# CaINv2_2.net
KiCad netlist of a schematic drawn in Altium Designer
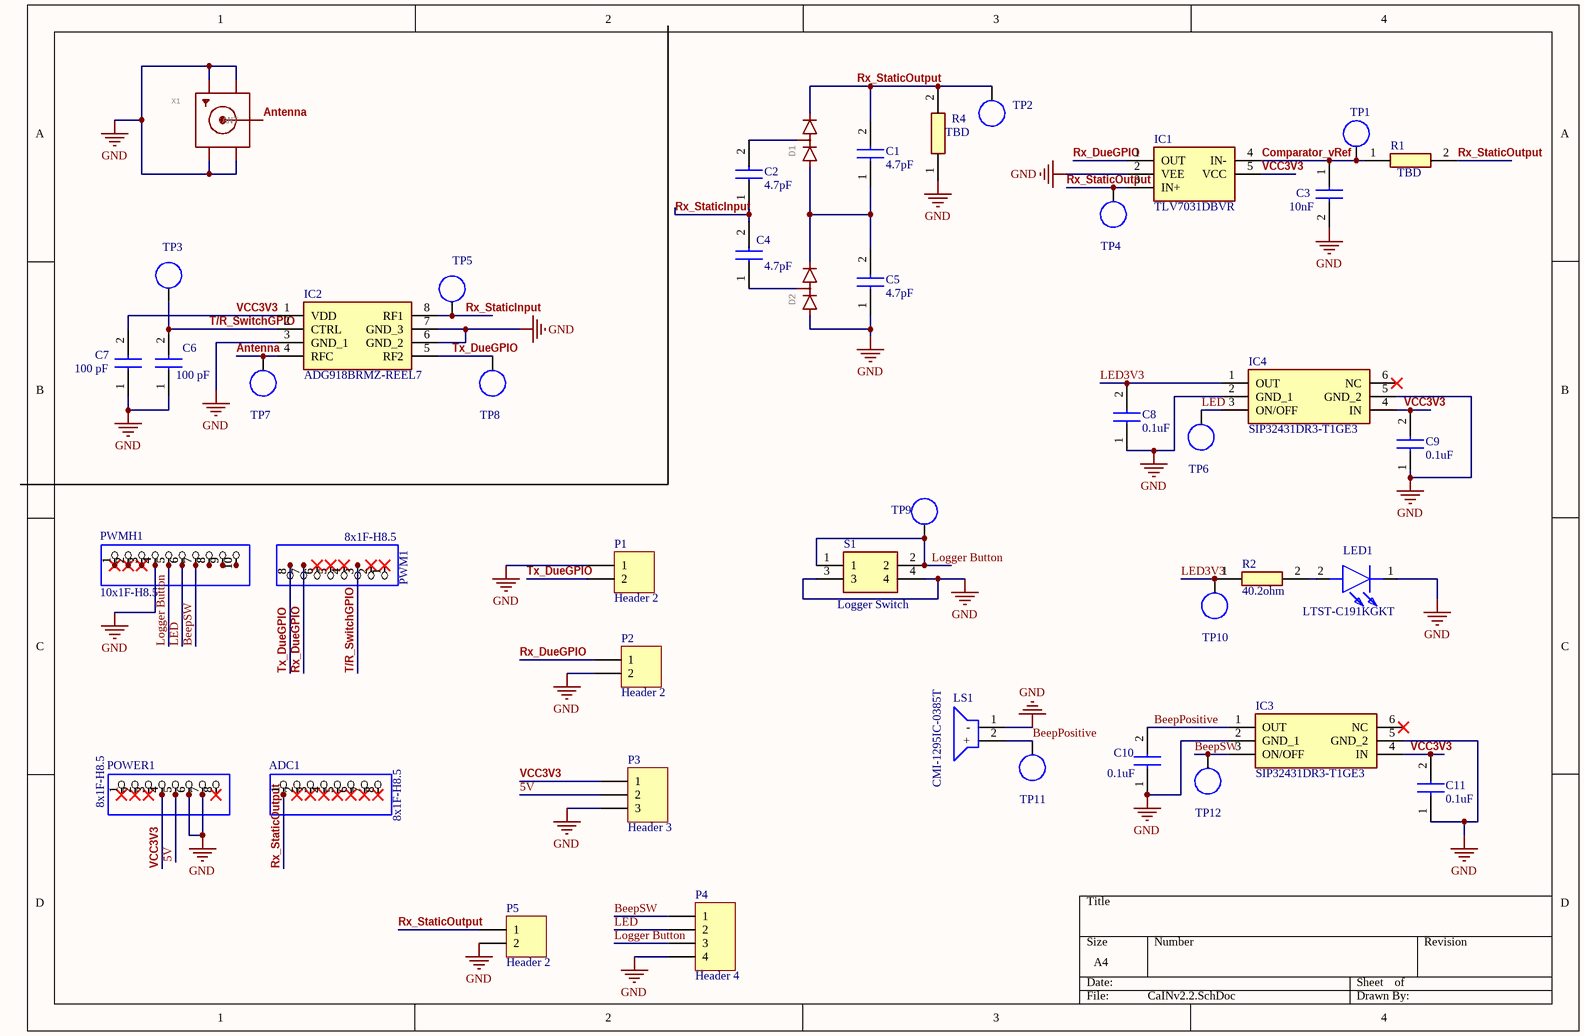
[diagram p0: CaINv2.2.SchDoc]

(export (version "E")
  (design (tool "Eeschema 10.0.6"))
  (components
    (comp (ref "ADC1")
      (value "8x1F-H8.5")
      (footprint "1X08")
      (libsource (lib "Arduino_Due") (part "PINHD-1X8"))
    )
    (comp (ref "C1")
      (value "4.7pF")
      (footprint "SamacSys:CAPC2012X145N")
      (description "Capacitor")
      (fields
        (field (name "MANUFACTURER_PART_NUMBER") "VJ0805A101JXBMC")
        (field (name "MOUSER PART NUMBER") "77-VJ0805A101JXBMC")
      )
      (libsource (lib "SamacSys") (part "VJ0805A101JXBMC"))
    )
    (comp (ref "C2")
      (value "4.7pF")
      (footprint "SamacSys:CAPC2012X145N")
      (description "Capacitor")
      (fields
        (field (name "MANUFACTURER_PART_NUMBER") "VJ0805A101JXBMC")
        (field (name "MOUSER PART NUMBER") "77-VJ0805A101JXBMC")
      )
      (libsource (lib "SamacSys") (part "VJ0805A101JXBMC"))
    )
    (comp (ref "C3")
      (value "10nF")
      (footprint "SamacSys:CAPC2012X145N")
      (description "Capacitor")
      (fields
        (field (name "MANUFACTURER_PART_NUMBER") "VJ0805Y103KXBAC")
        (field (name "MOUSER PART NUMBER") "77-VJ08Y100V103K")
      )
      (libsource (lib "SamacSys") (part "VJ0805Y103KXBAC"))
    )
    (comp (ref "C4")
      (value "4.7pF")
      (footprint "SamacSys:CAPC2012X145N")
      (description "Capacitor")
      (fields
        (field (name "MANUFACTURER_PART_NUMBER") "VJ0805A101JXBMC")
        (field (name "MOUSER PART NUMBER") "77-VJ0805A101JXBMC")
      )
      (libsource (lib "SamacSys") (part "VJ0805A101JXBMC"))
    )
    (comp (ref "C5")
      (value "4.7pF")
      (footprint "SamacSys:CAPC2012X145N")
      (description "Capacitor")
      (fields
        (field (name "MANUFACTURER_PART_NUMBER") "VJ0805A101JXBMC")
        (field (name "MOUSER PART NUMBER") "77-VJ0805A101JXBMC")
      )
      (libsource (lib "SamacSys") (part "VJ0805A101JXBMC"))
    )
    (comp (ref "C6")
      (value "100 pF")
      (footprint "SamacSys:CAPC2012X145N")
      (description "Capacitor")
      (fields
        (field (name "MANUFACTURER_PART_NUMBER") "VJ0805A101JXBMC")
        (field (name "MOUSER PART NUMBER") "77-VJ0805A101JXBMC")
      )
      (libsource (lib "SamacSys") (part "VJ0805A101JXBMC"))
    )
    (comp (ref "C7")
      (value "100 pF")
      (footprint "SamacSys:CAPC2012X145N")
      (description "Capacitor")
      (fields
        (field (name "MANUFACTURER_PART_NUMBER") "VJ0805A101JXBMC")
        (field (name "MOUSER PART NUMBER") "77-VJ0805A101JXBMC")
      )
      (libsource (lib "SamacSys") (part "VJ0805A101JXBMC"))
    )
    (comp (ref "C8")
      (value "0.1uF")
      (footprint "SamacSys:CAPC2012X145N")
      (description "Capacitor")
      (fields
        (field (name "MANUFACTURER_PART_NUMBER") "VJ0805A101JXBMC")
        (field (name "MOUSER PART NUMBER") "77-VJ0805A101JXBMC")
      )
      (libsource (lib "SamacSys") (part "VJ0805A101JXBMC"))
    )
    (comp (ref "C9")
      (value "0.1uF")
      (footprint "SamacSys:CAPC2012X145N")
      (description "Capacitor")
      (fields
        (field (name "MANUFACTURER_PART_NUMBER") "VJ0805A101JXBMC")
        (field (name "MOUSER PART NUMBER") "77-VJ0805A101JXBMC")
      )
      (libsource (lib "SamacSys") (part "VJ0805A101JXBMC"))
    )
    (comp (ref "C10")
      (value "0.1uF")
      (footprint "SamacSys:CAPC2012X145N")
      (description "Capacitor")
      (fields
        (field (name "MANUFACTURER_PART_NUMBER") "VJ0805A101JXBMC")
        (field (name "MOUSER PART NUMBER") "77-VJ0805A101JXBMC")
      )
      (libsource (lib "SamacSys") (part "VJ0805A101JXBMC"))
    )
    (comp (ref "C11")
      (value "0.1uF")
      (footprint "SamacSys:CAPC2012X145N")
      (description "Capacitor")
      (fields
        (field (name "MANUFACTURER_PART_NUMBER") "VJ0805A101JXBMC")
        (field (name "MOUSER PART NUMBER") "77-VJ0805A101JXBMC")
      )
      (libsource (lib "SamacSys") (part "VJ0805A101JXBMC"))
    )
    (comp (ref "D1")
      (value "RB706F-40FHT106")
      (footprint "SOT23")
      (description "2 Diodes - Cathode-Anode¦Cathode-Anode DIODE_2CACA-SOT23")
      (libsource (lib "RF_EHv1.1") (part "DIODE_2CACA-SOT23"))
    )
    (comp (ref "D2")
      (value "RB706F-40FHT106")
      (footprint "SOT23")
      (description "2 Diodes - Cathode-Anode¦Cathode-Anode DIODE_2CACA-SOT23")
      (libsource (lib "RF_EHv1.1") (part "DIODE_2CACA-SOT23"))
    )
    (comp (ref "IC1")
      (value "TLV7031DBVR")
      (footprint "SamacSys:SOT95P280X145-5N")
      (description "Integrated Circuit")
      (fields (field (name "MOUSER PART NUMBER") "595-TLV7031DBVR"))
      (libsource (lib "SamacSys") (part "TLV7031DBVR"))
    )
    (comp (ref "IC2")
      (value "ADG918BRMZ-REEL7")
      (footprint "SamacSys:SOP65P490X110-8N")
      (description "Integrated Circuit")
      (fields (field (name "MOUSER PART NUMBER") "584-ADG918BRMZ-R7"))
      (libsource (lib "SamacSys") (part "ADG918BRMZ-REEL7"))
    )
    (comp (ref "IC3")
      (value "SIP32431DR3-T1GE3")
      (footprint "SamacSys:SOT65P210X110-6N")
      (description "Integrated Circuit")
      (fields (field (name "MOUSER PART NUMBER") "781-SIP32431DR3-GE3"))
      (libsource (lib "SamacSys") (part "SIP32431DR3-T1GE3"))
    )
    (comp (ref "IC4")
      (value "SIP32431DR3-T1GE3")
      (footprint "SamacSys:SOT65P210X110-6N")
      (description "Integrated Circuit")
      (fields (field (name "MOUSER PART NUMBER") "781-SIP32431DR3-GE3"))
      (libsource (lib "SamacSys") (part "SIP32431DR3-T1GE3"))
    )
    (comp (ref "LED1")
      (value "LTST-C191KGKT")
      (footprint "SamacSys:LEDC1608X55N")
      (description "LED")
      (fields (field (name "MOUSER PART NUMBER") "859-LTST-C191KGKT"))
      (libsource (lib "*") (part "LTST-C191KGKT"))
    )
    (comp (ref "LS1")
      (value "CMI-1295IC-0385T")
      (footprint "SamacSys:CMI1295IC0385T")
      (description "Loudspeaker or Buzzer")
      (fields (field (name "MOUSER PART NUMBER") "490-CMI-1295IC-0385T"))
      (libsource (lib "*") (part "CMI-1295IC-0385T"))
    )
    (comp (ref "P1")
      (value "Header 2")
      (footprint "HDR1X2")
      (description "Header, 2-Pin")
      (fields (field (name "PUBLISHER") "Altium Limited"))
      (libsource (lib "常用元件集成库") (part "Header 2"))
    )
    (comp (ref "P2")
      (value "Header 2")
      (footprint "HDR1X2")
      (description "Header, 2-Pin")
      (fields (field (name "PUBLISHER") "Altium Limited"))
      (libsource (lib "常用元件集成库") (part "Header 2"))
    )
    (comp (ref "P3")
      (value "Header 3")
      (footprint "HDR1X3")
      (description "Header, 3-Pin")
      (fields (field (name "PUBLISHER") "Altium Limited"))
      (libsource (lib "常用元件集成库") (part "Header 3"))
    )
    (comp (ref "P4")
      (value "Header 4")
      (footprint "HDR1X4")
      (description "Header, 4-Pin")
      (fields (field (name "PUBLISHER") "Altium Limited"))
      (libsource (lib "常用元件集成库") (part "Header 4"))
    )
    (comp (ref "P5")
      (value "Header 2")
      (footprint "HDR1X2")
      (description "Header, 2-Pin")
      (fields (field (name "PUBLISHER") "Altium Limited"))
      (libsource (lib "常用元件集成库") (part "Header 2"))
    )
    (comp (ref "POWER1")
      (value "8x1F-H8.5")
      (footprint "1X08")
      (libsource (lib "Arduino_Due") (part "PINHD-1X8"))
    )
    (comp (ref "PWM1")
      (value "8x1F-H8.5")
      (footprint "1X08")
      (libsource (lib "Arduino_Due") (part "PINHD-1X8"))
    )
    (comp (ref "PWMH1")
      (value "10x1F-H8.5")
      (footprint "1X10")
      (libsource (lib "Arduino_Due") (part "PINHD-1X10"))
    )
    (comp (ref "R1")
      (value "TBD")
      (footprint "SamacSys:RESC2012X50N")
      (description "Resistor")
      (fields
        (field (name "MANUFACTURER_PART_NUMBER") "RCS0805100KFKEA")
        (field (name "MOUSER PART NUMBER") "71-RCS0805100KFKEA")
      )
      (libsource (lib "SamacSys") (part "RCS0805100KFKEA"))
    )
    (comp (ref "R2")
      (value "40.2ohm")
      (footprint "SamacSys:RESC1608X55N")
      (description "Resistor")
      (fields
        (field (name "MANUFACTURER_PART_NUMBER") "ERJ-3EKF40R2V")
        (field (name "MOUSER PART NUMBER") "667-ERJ-3EKF40R2V")
      )
      (libsource (lib "*") (part "ERJ-3EKF40R2V"))
    )
    (comp (ref "R4")
      (value "TBD")
      (footprint "SamacSys:RESC2012X50N")
      (description "Resistor")
      (fields
        (field (name "MANUFACTURER_PART_NUMBER") "RCS0805100KFKEA")
        (field (name "MOUSER PART NUMBER") "71-RCS0805100KFKEA")
      )
      (libsource (lib "") (part "RCS0805100KFKEA_1"))
    )
    (comp (ref "S1")
      (value "Logger Switch")
      (footprint "SamacSys:PTS645(SMT)")
      (description "SwitchPTS645SM43SMTR92LFS")
      (fields
        (field (name "MANUFACTURER_PART_NUMBER") "PTS645SM43SMTR92LFS")
        (field (name "MOUSER PART NUMBER") "611-PTS645SM43SMTR92")
      )
      (libsource (lib "*") (part "PTS645SM43SMTR92LFS"))
    )
    (comp (ref "TP1") (value "TP") (footprint "TestPoint") (libsource (lib "ReVibe_Z") (part "TestPoint")))
    (comp (ref "TP2") (value "TP") (footprint "TestPoint") (libsource (lib "ReVibe_Z") (part "TestPoint")))
    (comp (ref "TP3") (value "TP") (footprint "TestPoint") (libsource (lib "ReVibe_Z") (part "TestPoint")))
    (comp (ref "TP4") (value "TP") (footprint "TestPoint") (libsource (lib "ReVibe_Z") (part "TestPoint")))
    (comp (ref "TP5") (value "TP") (footprint "TestPoint") (libsource (lib "ReVibe_Z") (part "TestPoint")))
    (comp (ref "TP6") (value "TP") (footprint "TestPoint") (libsource (lib "ReVibe_Z") (part "TestPoint")))
    (comp (ref "TP7") (value "TP") (footprint "TestPoint") (libsource (lib "ReVibe_Z") (part "TestPoint")))
    (comp (ref "TP8") (value "TP") (footprint "TestPoint") (libsource (lib "ReVibe_Z") (part "TestPoint")))
    (comp (ref "TP9") (value "TP") (footprint "TestPoint") (libsource (lib "ReVibe_Z") (part "TestPoint")))
    (comp (ref "TP10") (value "TP") (footprint "TestPoint") (libsource (lib "ReVibe_Z") (part "TestPoint")))
    (comp (ref "TP11") (value "TP") (footprint "TestPoint") (libsource (lib "ReVibe_Z") (part "TestPoint")))
    (comp (ref "TP12") (value "TP") (footprint "TestPoint") (libsource (lib "ReVibe_Z") (part "TestPoint")))
    (comp (ref "X1")
      (value "SMACONNECTOR_EDGE")
      (footprint "SMA_EDGELAUNCH")
      (description "SMA Connector   90掳 DIP SMA Connector, 50 Ohm (4UConnector: 07259)")
      (libsource (lib "RF_EHv1.1") (part "SMACONNECTOR_EDGE"))
    )
  )
  (nets
    (net (code "1") (name "/5V") (class "Default")
      (node (ref "P3") (pin "2") (pinfunction "2_2") (pintype "passive"))
      (node (ref "POWER1") (pin "5") (pinfunction "5_5") (pintype "passive"))
    )
    (net (code "2") (name "/Antenna") (class "Default")
      (node (ref "IC2") (pin "4") (pinfunction "RFC_4") (pintype "passive"))
      (node (ref "TP7") (pin "TP") (pintype "passive"))
      (node (ref "X1") (pin "P") (pinfunction "ANT_P") (pintype "bidirectional"))
    )
    (net (code "3") (name "/BeepPositive") (class "Default")
      (node (ref "C10") (pin "2") (pinfunction "2_2") (pintype "passive"))
      (node (ref "IC3") (pin "1") (pinfunction "OUT_1") (pintype "passive"))
      (node (ref "LS1") (pin "2") (pinfunction "+_2") (pintype "passive"))
      (node (ref "TP11") (pin "TP") (pintype "passive"))
    )
    (net (code "4") (name "/BeepSW") (class "Default")
      (node (ref "IC3") (pin "3") (pinfunction "ON/OFF_3") (pintype "passive"))
      (node (ref "P4") (pin "1") (pinfunction "1_1") (pintype "passive"))
      (node (ref "PWMH1") (pin "7") (pinfunction "7_7") (pintype "passive"))
      (node (ref "TP12") (pin "TP") (pintype "passive"))
    )
    (net (code "5") (name "/Comparator_vRef") (class "Default")
      (node (ref "C3") (pin "1") (pinfunction "1_1") (pintype "passive"))
      (node (ref "IC1") (pin "4") (pinfunction "IN-_4") (pintype "passive"))
      (node (ref "R1") (pin "1") (pinfunction "1_1") (pintype "passive"))
      (node (ref "TP1") (pin "TP") (pintype "passive"))
    )
    (net (code "6") (name "/LED") (class "Default")
      (node (ref "IC4") (pin "3") (pinfunction "ON/OFF_3") (pintype "passive"))
      (node (ref "P4") (pin "2") (pinfunction "2_2") (pintype "passive"))
      (node (ref "PWMH1") (pin "6") (pinfunction "6_6") (pintype "passive"))
      (node (ref "TP6") (pin "TP") (pintype "passive"))
    )
    (net (code "7") (name "/LED3V3") (class "Default")
      (node (ref "C8") (pin "2") (pinfunction "2_2") (pintype "passive"))
      (node (ref "IC4") (pin "1") (pinfunction "OUT_1") (pintype "passive"))
      (node (ref "R2") (pin "1") (pinfunction "1_1") (pintype "passive"))
      (node (ref "TP10") (pin "TP") (pintype "passive"))
    )
    (net (code "8") (name "/Logger Button") (class "Default")
      (node (ref "P4") (pin "3") (pinfunction "3_3") (pintype "passive"))
      (node (ref "PWMH1") (pin "5") (pinfunction "5_5") (pintype "passive"))
      (node (ref "S1") (pin "1") (pinfunction "1_1") (pintype "passive"))
      (node (ref "S1") (pin "2") (pinfunction "2_2") (pintype "passive"))
      (node (ref "TP9") (pin "TP") (pintype "passive"))
    )
    (net (code "9") (name "/Rx_DueGPIO") (class "Default")
      (node (ref "IC1") (pin "1") (pinfunction "OUT_1") (pintype "passive"))
      (node (ref "P2") (pin "1") (pinfunction "1_1") (pintype "passive"))
      (node (ref "PWM1") (pin "7") (pinfunction "7_7") (pintype "passive"))
    )
    (net (code "10") (name "/Rx_StaticInput") (class "Default")
      (node (ref "C2") (pin "1") (pinfunction "1_1") (pintype "passive"))
      (node (ref "C4") (pin "2") (pinfunction "2_2") (pintype "passive"))
      (node (ref "IC2") (pin "8") (pinfunction "RF1_8") (pintype "passive"))
      (node (ref "TP5") (pin "TP") (pintype "passive"))
    )
    (net (code "11") (name "/Rx_StaticOutput") (class "Default")
      (node (ref "ADC1") (pin "1") (pinfunction "1_1") (pintype "passive"))
      (node (ref "C1") (pin "2") (pinfunction "2_2") (pintype "passive"))
      (node (ref "D1") (pin "2") (pinfunction "C_2") (pintype "passive"))
      (node (ref "IC1") (pin "3") (pinfunction "IN+_3") (pintype "passive"))
      (node (ref "P5") (pin "1") (pinfunction "1_1") (pintype "passive"))
      (node (ref "R1") (pin "2") (pinfunction "2_2") (pintype "passive"))
      (node (ref "R4") (pin "2") (pinfunction "2_2") (pintype "passive"))
      (node (ref "TP2") (pin "TP") (pintype "passive"))
      (node (ref "TP4") (pin "TP") (pintype "passive"))
    )
    (net (code "12") (name "/Tx_DueGPIO") (class "Default")
      (node (ref "IC2") (pin "5") (pinfunction "RF2_5") (pintype "passive"))
      (node (ref "P1") (pin "2") (pinfunction "2_2") (pintype "passive"))
      (node (ref "PWM1") (pin "8") (pinfunction "8_8") (pintype "passive"))
      (node (ref "TP8") (pin "TP") (pintype "passive"))
    )
    (net (code "13") (name "/T{slash}R_SwitchGPIO") (class "Default")
      (node (ref "C6") (pin "2") (pinfunction "2_2") (pintype "passive"))
      (node (ref "IC2") (pin "2") (pinfunction "CTRL_2") (pintype "passive"))
      (node (ref "PWM1") (pin "3") (pinfunction "3_3") (pintype "passive"))
      (node (ref "TP3") (pin "TP") (pintype "passive"))
    )
    (net (code "14") (name "/VCC3V3") (class "Default")
      (node (ref "C11") (pin "2") (pinfunction "2_2") (pintype "passive"))
      (node (ref "C7") (pin "2") (pinfunction "2_2") (pintype "passive"))
      (node (ref "C9") (pin "2") (pinfunction "2_2") (pintype "passive"))
      (node (ref "IC1") (pin "5") (pinfunction "VCC_5") (pintype "passive"))
      (node (ref "IC2") (pin "1") (pinfunction "VDD_1") (pintype "passive"))
      (node (ref "IC3") (pin "4") (pinfunction "IN_4") (pintype "passive"))
      (node (ref "IC4") (pin "4") (pinfunction "IN_4") (pintype "passive"))
      (node (ref "P3") (pin "1") (pinfunction "1_1") (pintype "passive"))
      (node (ref "POWER1") (pin "4") (pinfunction "4_4") (pintype "passive"))
    )
    (net (code "15") (name "GND") (class "Default")
      (node (ref "C10") (pin "1") (pinfunction "1_1") (pintype "passive"))
      (node (ref "C11") (pin "1") (pinfunction "1_1") (pintype "passive"))
      (node (ref "C3") (pin "2") (pinfunction "2_2") (pintype "passive"))
      (node (ref "C5") (pin "1") (pinfunction "1_1") (pintype "passive"))
      (node (ref "C6") (pin "1") (pinfunction "1_1") (pintype "passive"))
      (node (ref "C7") (pin "1") (pinfunction "1_1") (pintype "passive"))
      (node (ref "C8") (pin "1") (pinfunction "1_1") (pintype "passive"))
      (node (ref "C9") (pin "1") (pinfunction "1_1") (pintype "passive"))
      (node (ref "D2") (pin "1") (pinfunction "A_1") (pintype "passive"))
      (node (ref "IC1") (pin "2") (pinfunction "VEE_2") (pintype "passive"))
      (node (ref "IC2") (pin "3") (pinfunction "GND_1_3") (pintype "passive"))
      (node (ref "IC2") (pin "6") (pinfunction "GND_2_6") (pintype "passive"))
      (node (ref "IC2") (pin "7") (pinfunction "GND_3_7") (pintype "passive"))
      (node (ref "IC3") (pin "2") (pinfunction "GND_1_2") (pintype "passive"))
      (node (ref "IC3") (pin "5") (pinfunction "GND_2_5") (pintype "passive"))
      (node (ref "IC4") (pin "2") (pinfunction "GND_1_2") (pintype "passive"))
      (node (ref "IC4") (pin "5") (pinfunction "GND_2_5") (pintype "passive"))
      (node (ref "LED1") (pin "1") (pinfunction "K_1") (pintype "passive"))
      (node (ref "LS1") (pin "1") (pinfunction "-_1") (pintype "passive"))
      (node (ref "P1") (pin "1") (pinfunction "1_1") (pintype "passive"))
      (node (ref "P2") (pin "2") (pinfunction "2_2") (pintype "passive"))
      (node (ref "P3") (pin "3") (pinfunction "3_3") (pintype "passive"))
      (node (ref "P4") (pin "4") (pinfunction "4_4") (pintype "passive"))
      (node (ref "P5") (pin "2") (pinfunction "2_2") (pintype "passive"))
      (node (ref "POWER1") (pin "6") (pinfunction "6_6") (pintype "passive"))
      (node (ref "POWER1") (pin "7") (pinfunction "7_7") (pintype "passive"))
      (node (ref "PWMH1") (pin "4") (pinfunction "4_4") (pintype "passive"))
      (node (ref "R4") (pin "1") (pinfunction "1_1") (pintype "passive"))
      (node (ref "S1") (pin "3") (pinfunction "3_3") (pintype "passive"))
      (node (ref "S1") (pin "4") (pinfunction "4_4") (pintype "passive"))
      (node (ref "X1") (pin "GND@1") (pinfunction "GND4_GND@1") (pintype "power_in"))
      (node (ref "X1") (pin "GND@2") (pinfunction "GND3_GND@2") (pintype "power_in"))
      (node (ref "X1") (pin "GND@3") (pinfunction "GND2_GND@3") (pintype "power_in"))
      (node (ref "X1") (pin "GND@4") (pinfunction "GND1_GND@4") (pintype "power_in"))
    )
    (net (code "16") (name "Net-(D1-A)") (class "Default")
      (node (ref "C1") (pin "1") (pinfunction "1_1") (pintype "passive"))
      (node (ref "C5") (pin "2") (pinfunction "2_2") (pintype "passive"))
      (node (ref "D1") (pin "1") (pinfunction "A_1") (pintype "passive"))
      (node (ref "D2") (pin "2") (pinfunction "C_2") (pintype "passive"))
    )
    (net (code "17") (name "Net-(D1-AC)") (class "Default")
      (node (ref "C2") (pin "2") (pinfunction "2_2") (pintype "passive"))
      (node (ref "D1") (pin "3") (pinfunction "AC_3") (pintype "passive"))
    )
    (net (code "18") (name "Net-(D2-AC)") (class "Default")
      (node (ref "C4") (pin "1") (pinfunction "1_1") (pintype "passive"))
      (node (ref "D2") (pin "3") (pinfunction "AC_3") (pintype "passive"))
    )
    (net (code "19") (name "Net-(LED1-A)") (class "Default")
      (node (ref "LED1") (pin "2") (pinfunction "A_2") (pintype "passive"))
      (node (ref "R2") (pin "2") (pinfunction "2_2") (pintype "passive"))
    )
    (net (code "20") (name "Net-(PWMH1-Pad8)") (class "Default")
      (node (ref "PWMH1") (pin "8") (pinfunction "8_8") (pintype "passive"))
    )
    (net (code "21") (name "Net-(PWMH1-Pad9)") (class "Default")
      (node (ref "PWMH1") (pin "9") (pinfunction "9_9") (pintype "passive"))
    )
    (net (code "22") (name "Net-(PWMH1-Pad10)") (class "Default")
      (node (ref "PWMH1") (pin "10") (pinfunction "10_10") (pintype "passive"))
    )
    (net (code "23") (name "unconnected-(ADC1-Pad2)") (class "Default")
      (node (ref "ADC1") (pin "2") (pinfunction "2_2") (pintype "passive+no_connect"))
    )
    (net (code "24") (name "unconnected-(ADC1-Pad3)") (class "Default")
      (node (ref "ADC1") (pin "3") (pinfunction "3_3") (pintype "passive+no_connect"))
    )
    (net (code "25") (name "unconnected-(ADC1-Pad4)") (class "Default")
      (node (ref "ADC1") (pin "4") (pinfunction "4_4") (pintype "passive+no_connect"))
    )
    (net (code "26") (name "unconnected-(ADC1-Pad5)") (class "Default")
      (node (ref "ADC1") (pin "5") (pinfunction "5_5") (pintype "passive+no_connect"))
    )
    (net (code "27") (name "unconnected-(ADC1-Pad6)") (class "Default")
      (node (ref "ADC1") (pin "6") (pinfunction "6_6") (pintype "passive+no_connect"))
    )
    (net (code "28") (name "unconnected-(ADC1-Pad7)") (class "Default")
      (node (ref "ADC1") (pin "7") (pinfunction "7_7") (pintype "passive+no_connect"))
    )
    (net (code "29") (name "unconnected-(ADC1-Pad8)") (class "Default")
      (node (ref "ADC1") (pin "8") (pinfunction "8_8") (pintype "passive+no_connect"))
    )
    (net (code "30") (name "unconnected-(IC3-NC-Pad6)") (class "Default")
      (node (ref "IC3") (pin "6") (pinfunction "NC_6") (pintype "passive+no_connect"))
    )
    (net (code "31") (name "unconnected-(IC4-NC-Pad6)") (class "Default")
      (node (ref "IC4") (pin "6") (pinfunction "NC_6") (pintype "passive+no_connect"))
    )
    (net (code "32") (name "unconnected-(POWER1-Pad1)") (class "Default")
      (node (ref "POWER1") (pin "1") (pinfunction "1_1") (pintype "passive+no_connect"))
    )
    (net (code "33") (name "unconnected-(POWER1-Pad2)") (class "Default")
      (node (ref "POWER1") (pin "2") (pinfunction "2_2") (pintype "passive+no_connect"))
    )
    (net (code "34") (name "unconnected-(POWER1-Pad3)") (class "Default")
      (node (ref "POWER1") (pin "3") (pinfunction "3_3") (pintype "passive+no_connect"))
    )
    (net (code "35") (name "unconnected-(POWER1-Pad8)") (class "Default")
      (node (ref "POWER1") (pin "8") (pinfunction "8_8") (pintype "passive+no_connect"))
    )
    (net (code "36") (name "unconnected-(PWM1-Pad1)") (class "Default")
      (node (ref "PWM1") (pin "1") (pinfunction "1_1") (pintype "passive+no_connect"))
    )
    (net (code "37") (name "unconnected-(PWM1-Pad2)") (class "Default")
      (node (ref "PWM1") (pin "2") (pinfunction "2_2") (pintype "passive+no_connect"))
    )
    (net (code "38") (name "unconnected-(PWM1-Pad4)") (class "Default")
      (node (ref "PWM1") (pin "4") (pinfunction "4_4") (pintype "passive+no_connect"))
    )
    (net (code "39") (name "unconnected-(PWM1-Pad5)") (class "Default")
      (node (ref "PWM1") (pin "5") (pinfunction "5_5") (pintype "passive+no_connect"))
    )
    (net (code "40") (name "unconnected-(PWM1-Pad6)") (class "Default")
      (node (ref "PWM1") (pin "6") (pinfunction "6_6") (pintype "passive+no_connect"))
    )
    (net (code "41") (name "unconnected-(PWMH1-Pad1)") (class "Default")
      (node (ref "PWMH1") (pin "1") (pinfunction "1_1") (pintype "passive+no_connect"))
    )
    (net (code "42") (name "unconnected-(PWMH1-Pad2)") (class "Default")
      (node (ref "PWMH1") (pin "2") (pinfunction "2_2") (pintype "passive+no_connect"))
    )
    (net (code "43") (name "unconnected-(PWMH1-Pad3)") (class "Default")
      (node (ref "PWMH1") (pin "3") (pinfunction "3_3") (pintype "passive+no_connect"))
    )
  )
)
